# Sheet1.net
KiCad netlist of a schematic drawn in Altium Designer
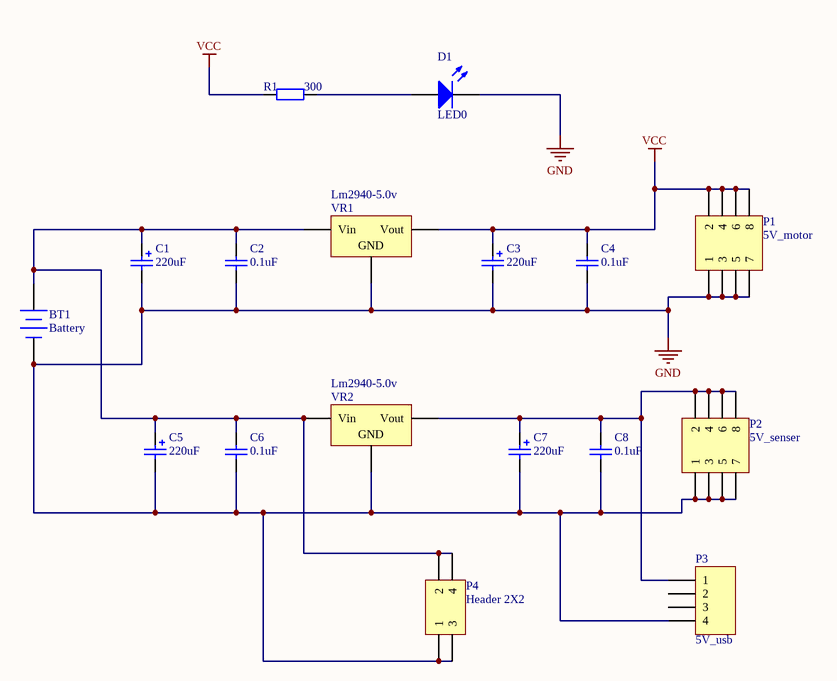
[diagram p0: Sheet1.SchDoc]

(export (version "E")
  (design (tool "Eeschema 10.0.6"))
  (components
    (comp (ref "BT1")
      (value "Battery")
      (footprint "PCB_LIB:DC5V-1")
      (description "Multicell Battery")
      (fields (field (name "PUBLISHER") "Altium Limited"))
      (libsource (lib "Miscellaneous Devices") (part "Battery"))
    )
    (comp (ref "C1")
      (value "220uF")
      (footprint "PCB_LIB:ELEC-10UF")
      (description "Polarized Capacitor (Axial)")
      (fields (field (name "Comment") "Cap Pol2") (field (name "PUBLISHER") "Altium Limited"))
      (libsource (lib "Miscellaneous Devices") (part "Cap Pol2"))
    )
    (comp (ref "C2")
      (value "0.1uF")
      (footprint "PCB_LIB:CAP-DIP")
      (description "Capacitor")
      (fields (field (name "Comment") "Cap") (field (name "PUBLISHER") "Altium Limited"))
      (libsource (lib "Miscellaneous Devices") (part "Cap"))
    )
    (comp (ref "C3")
      (value "220uF")
      (footprint "PCB_LIB:ELEC-10UF")
      (description "Polarized Capacitor (Axial)")
      (fields (field (name "Comment") "Cap Pol2") (field (name "PUBLISHER") "Altium Limited"))
      (libsource (lib "Miscellaneous Devices") (part "Cap Pol2"))
    )
    (comp (ref "C4")
      (value "0.1uF")
      (footprint "CAP-DIP")
      (description "Capacitor")
      (fields (field (name "Comment") "Cap") (field (name "PUBLISHER") "Altium Limited"))
      (libsource (lib "Miscellaneous Devices") (part "Cap"))
    )
    (comp (ref "C5")
      (value "220uF")
      (footprint "PCB_LIB:ELEC-10UF")
      (description "Polarized Capacitor (Axial)")
      (fields (field (name "Comment") "Cap Pol2") (field (name "PUBLISHER") "Altium Limited"))
      (libsource (lib "Miscellaneous Devices") (part "Cap Pol2"))
    )
    (comp (ref "C6")
      (value "0.1uF")
      (footprint "PCB_LIB:CAP-DIP")
      (description "Capacitor")
      (fields (field (name "Comment") "Cap") (field (name "PUBLISHER") "Altium Limited"))
      (libsource (lib "Miscellaneous Devices") (part "Cap"))
    )
    (comp (ref "C7")
      (value "220uF")
      (footprint "PCB_LIB:ELEC-10UF")
      (description "Polarized Capacitor (Axial)")
      (fields (field (name "Comment") "Cap Pol2") (field (name "PUBLISHER") "Altium Limited"))
      (libsource (lib "Miscellaneous Devices") (part "Cap Pol2"))
    )
    (comp (ref "C8")
      (value "0.1uF")
      (footprint "PCB_LIB:CAP-DIP")
      (description "Capacitor")
      (fields (field (name "Comment") "Cap") (field (name "PUBLISHER") "Altium Limited"))
      (libsource (lib "Miscellaneous Devices") (part "Cap"))
    )
    (comp (ref "D1")
      (value "LED0")
      (footprint "PCB_LIB:LED-DIP")
      (description "Typical INFRARED GaAs LED")
      (fields (field (name "PUBLISHER") "Altium Limited"))
      (libsource (lib "Miscellaneous Devices") (part "LED0"))
    )
    (comp (ref "P1")
      (value "5V_motor")
      (footprint "HDR2X4")
      (description "Header, 4-Pin, Dual row")
      (fields (field (name "PUBLISHER") "Altium Limited"))
      (libsource (lib "") (part "Header 4X2_1"))
    )
    (comp (ref "P2")
      (value "5V_senser")
      (footprint "HDR2X4")
      (description "Header, 4-Pin, Dual row")
      (fields (field (name "PUBLISHER") "Altium Limited"))
      (libsource (lib "Miscellaneous Connectors") (part "Header 4X2"))
    )
    (comp (ref "P3")
      (value "5V_usb")
      (footprint "PCB_LIB:USB")
      (description "Header, 4-Pin")
      (fields (field (name "PUBLISHER") "Altium Limited"))
      (libsource (lib "Miscellaneous Connectors") (part "Header 4"))
    )
    (comp (ref "P4")
      (value "Header 2X2")
      (footprint "HDR2X2")
      (description "Header, 2-Pin, Dual row")
      (fields (field (name "PUBLISHER") "Altium Limited"))
      (libsource (lib "Miscellaneous Connectors") (part "Header 2X2"))
    )
    (comp (ref "R1")
      (value "300")
      (footprint "PCB_LIB:RES-300MIL")
      (description "Resistor")
      (fields (field (name "Comment") "Res2") (field (name "PUBLISHER") "Altium Limited"))
      (libsource (lib "Miscellaneous Devices") (part "Res2"))
    )
    (comp (ref "VR1")
      (value "Lm2940-5.0v")
      (footprint "7805-DIP1")
      (description "Voltage Regulator")
      (fields (field (name "PUBLISHER") "Altium Limited"))
      (libsource (lib "Miscellaneous Devices") (part "Volt Reg"))
    )
    (comp (ref "VR2")
      (value "Lm2940-5.0v")
      (footprint "7805-DIP1")
      (description "Voltage Regulator")
      (fields (field (name "PUBLISHER") "Altium Limited"))
      (libsource (lib "Miscellaneous Devices") (part "Volt Reg"))
    )
  )
  (nets
    (net (code "1") (name "GND") (class "Default")
      (node (ref "BT1") (pin "2") (pinfunction "-_2") (pintype "passive"))
      (node (ref "C1") (pin "2") (pinfunction "2_2") (pintype "passive"))
      (node (ref "C2") (pin "1") (pinfunction "1_1") (pintype "passive"))
      (node (ref "C3") (pin "2") (pinfunction "2_2") (pintype "passive"))
      (node (ref "C4") (pin "1") (pinfunction "1_1") (pintype "passive"))
      (node (ref "C5") (pin "2") (pinfunction "2_2") (pintype "passive"))
      (node (ref "C6") (pin "1") (pinfunction "1_1") (pintype "passive"))
      (node (ref "C7") (pin "2") (pinfunction "2_2") (pintype "passive"))
      (node (ref "C8") (pin "1") (pinfunction "1_1") (pintype "passive"))
      (node (ref "D1") (pin "2") (pinfunction "K_2") (pintype "passive"))
      (node (ref "P1") (pin "1") (pinfunction "1_1") (pintype "passive"))
      (node (ref "P1") (pin "3") (pinfunction "3_3") (pintype "passive"))
      (node (ref "P1") (pin "5") (pinfunction "5_5") (pintype "passive"))
      (node (ref "P1") (pin "7") (pinfunction "7_7") (pintype "passive"))
      (node (ref "P2") (pin "1") (pinfunction "1_1") (pintype "passive"))
      (node (ref "P2") (pin "3") (pinfunction "3_3") (pintype "passive"))
      (node (ref "P2") (pin "5") (pinfunction "5_5") (pintype "passive"))
      (node (ref "P2") (pin "7") (pinfunction "7_7") (pintype "passive"))
      (node (ref "P3") (pin "4") (pinfunction "4_4") (pintype "passive"))
      (node (ref "P4") (pin "1") (pinfunction "1_1") (pintype "passive"))
      (node (ref "P4") (pin "3") (pinfunction "3_3") (pintype "passive"))
      (node (ref "VR1") (pin "2") (pinfunction "GND_2") (pintype "passive"))
      (node (ref "VR2") (pin "2") (pinfunction "GND_2") (pintype "passive"))
    )
    (net (code "2") (name "Net-(BT1-+)") (class "Default")
      (node (ref "BT1") (pin "1") (pinfunction "+_1") (pintype "power_in"))
      (node (ref "C1") (pin "1") (pinfunction "1_1") (pintype "passive"))
      (node (ref "C2") (pin "2") (pinfunction "2_2") (pintype "passive"))
      (node (ref "C5") (pin "1") (pinfunction "1_1") (pintype "passive"))
      (node (ref "C6") (pin "2") (pinfunction "2_2") (pintype "passive"))
      (node (ref "P4") (pin "2") (pinfunction "2_2") (pintype "passive"))
      (node (ref "P4") (pin "4") (pinfunction "4_4") (pintype "passive"))
      (node (ref "VR1") (pin "1") (pinfunction "Vin_1") (pintype "passive"))
      (node (ref "VR2") (pin "1") (pinfunction "Vin_1") (pintype "passive"))
    )
    (net (code "3") (name "Net-(D1-A)") (class "Default")
      (node (ref "D1") (pin "1") (pinfunction "A_1") (pintype "passive"))
      (node (ref "R1") (pin "2") (pinfunction "2_2") (pintype "passive"))
    )
    (net (code "4") (name "Net-(VR2-Vout)") (class "Default")
      (node (ref "C7") (pin "1") (pinfunction "1_1") (pintype "passive"))
      (node (ref "C8") (pin "2") (pinfunction "2_2") (pintype "passive"))
      (node (ref "P2") (pin "2") (pinfunction "2_2") (pintype "passive"))
      (node (ref "P2") (pin "4") (pinfunction "4_4") (pintype "passive"))
      (node (ref "P2") (pin "6") (pinfunction "6_6") (pintype "passive"))
      (node (ref "P2") (pin "8") (pinfunction "8_8") (pintype "passive"))
      (node (ref "P3") (pin "1") (pinfunction "1_1") (pintype "passive"))
      (node (ref "VR2") (pin "3") (pinfunction "Vout_3") (pintype "passive"))
    )
    (net (code "5") (name "VCC") (class "Default")
      (node (ref "C3") (pin "1") (pinfunction "1_1") (pintype "passive"))
      (node (ref "C4") (pin "2") (pinfunction "2_2") (pintype "passive"))
      (node (ref "P1") (pin "2") (pinfunction "2_2") (pintype "passive"))
      (node (ref "P1") (pin "4") (pinfunction "4_4") (pintype "passive"))
      (node (ref "P1") (pin "6") (pinfunction "6_6") (pintype "passive"))
      (node (ref "P1") (pin "8") (pinfunction "8_8") (pintype "passive"))
      (node (ref "R1") (pin "1") (pinfunction "1_1") (pintype "passive"))
      (node (ref "VR1") (pin "3") (pinfunction "Vout_3") (pintype "passive"))
    )
    (net (code "6") (name "unconnected-(BT1-GND-Pad3)") (class "Default")
      (node (ref "BT1") (pin "3") (pinfunction "GND_3") (pintype "passive"))
    )
    (net (code "7") (name "unconnected-(P3-Pad2)") (class "Default")
      (node (ref "P3") (pin "2") (pinfunction "2_2") (pintype "passive"))
    )
    (net (code "8") (name "unconnected-(P3-Pad3)") (class "Default")
      (node (ref "P3") (pin "3") (pinfunction "3_3") (pintype "passive"))
    )
  )
)
